# INA219_CH2.net
KiCad netlist of a schematic drawn in Altium Designer
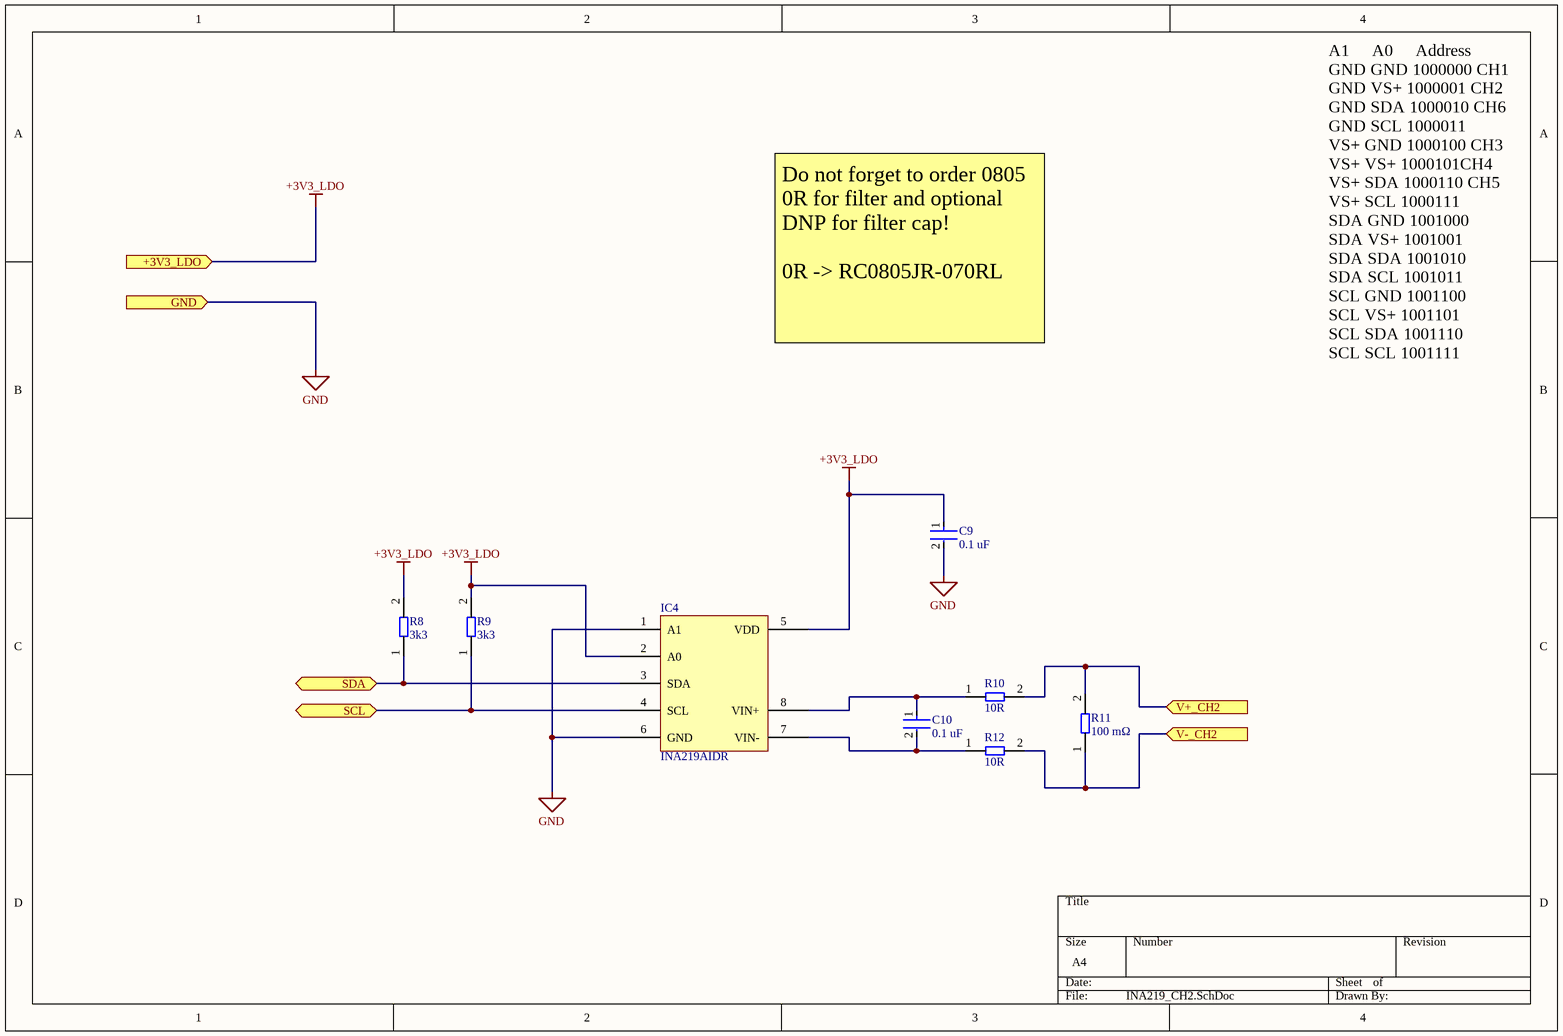
[diagram p0: INA219_CH2.SchDoc]

(export (version "E")
  (design (tool "Eeschema 10.0.6"))
  (components
    (comp (ref "C9")
      (value "0.1 uF")
      (footprint "FP-C0805C-DN-MFG")
      (description "C0805 0.10 μF X7R 30ppm/°C 20.00% 50 V C0805C104M5RAC")
      (fields
        (field (name "MANUFACTURER PART NUMBER") "C0805C104M5RAC")
        (field (name "MANUFACTURER") "KEMET")
      )
      (libsource (lib "Altium Content Vault") (part "b4654b650e69147ec39a6b967a45e02"))
    )
    (comp (ref "C10")
      (value "0.1 uF")
      (footprint "FP-C0805C-DN-MFG")
      (description "C0805 0.10 μF X7R 30ppm/°C 20.00% 50 V C0805C104M5RAC")
      (fields
        (field (name "MANUFACTURER PART NUMBER") "C0805C104M5RAC")
        (field (name "MANUFACTURER") "KEMET")
      )
      (libsource (lib "Altium Content Vault") (part "b4654b650e69147ec39a6b967a45e02"))
    )
    (comp (ref "IC4")
      (value "INA219AIDR")
      (footprint "INA219AIDR")
      (description "Current & Power Monitors & Regulators Zero-Drift,Bi-Dir Crnt/Pwr Monitor")
      (libsource (lib "Callisto Control Board") (part "INA219AIDR"))
    )
    (comp (ref "R8")
      (value "3k3")
      (footprint "0805 Resistor - IPC A")
      (description "Thick Film Resistors - SMD 3.3 kOhms 125 mW 0805 1%\r\nRE0805FRE073K3L")
      (libsource (lib "Callisto Control Board") (part "RE0805FRE073K3L"))
    )
    (comp (ref "R9")
      (value "3k3")
      (footprint "0805 Resistor - IPC A")
      (description "Thick Film Resistors - SMD 3.3 kOhms 125 mW 0805 1%\r\nRE0805FRE073K3L")
      (libsource (lib "Callisto Control Board") (part "RE0805FRE073K3L"))
    )
    (comp (ref "R10")
      (value "10R")
      (footprint "0805 Resistor - IPC A")
      (description "Thick Film Resistors - SMD 10 Ohms 125 mW 0805 1%\r\nRC0805FR-0710RL")
      (libsource (lib "Callisto Control Board") (part "RC0805FR-0710RL"))
    )
    (comp (ref "R11")
      (value "100 mΩ")
      (footprint "PE2512FKM070R1L")
      (description "Current Sense Resistors - SMD 100 mOhms 1 Watt 1 % 75 ppm/C AEC-Q200\r\nPE2512FKM070R1L")
      (libsource (lib "Callisto Control Board") (part "PE2512FKM070R1L"))
    )
    (comp (ref "R12")
      (value "10R")
      (footprint "0805 Resistor - IPC A")
      (description "Thick Film Resistors - SMD 10 Ohms 125 mW 0805 1%\r\nRC0805FR-0710RL")
      (libsource (lib "Callisto Control Board") (part "RC0805FR-0710RL"))
    )
  )
  (nets
    (net (code "1") (name "+3V3_LDO") (class "Default")
      (node (ref "C9") (pin "1") (pinfunction "1_1") (pintype "passive"))
      (node (ref "IC4") (pin "2") (pinfunction "A0_2") (pintype "passive"))
      (node (ref "IC4") (pin "5") (pinfunction "VDD_5") (pintype "passive"))
      (node (ref "R8") (pin "2") (pintype "passive"))
      (node (ref "R9") (pin "2") (pintype "passive"))
    )
    (net (code "2") (name "/SCL") (class "Default")
      (node (ref "IC4") (pin "4") (pinfunction "SCL_4") (pintype "passive"))
      (node (ref "R9") (pin "1") (pintype "passive"))
    )
    (net (code "3") (name "/SDA") (class "Default")
      (node (ref "IC4") (pin "3") (pinfunction "SDA_3") (pintype "passive"))
      (node (ref "R8") (pin "1") (pintype "passive"))
    )
    (net (code "4") (name "/V+_CH2") (class "Default")
      (node (ref "R10") (pin "2") (pintype "passive"))
      (node (ref "R11") (pin "2") (pintype "passive"))
    )
    (net (code "5") (name "/V-_CH2") (class "Default")
      (node (ref "R11") (pin "1") (pintype "passive"))
      (node (ref "R12") (pin "2") (pintype "passive"))
    )
    (net (code "6") (name "GND") (class "Default")
      (node (ref "C9") (pin "2") (pinfunction "2_2") (pintype "passive"))
      (node (ref "IC4") (pin "1") (pinfunction "A1_1") (pintype "passive"))
      (node (ref "IC4") (pin "6") (pinfunction "GND_6") (pintype "passive"))
    )
    (net (code "7") (name "Net-(IC4-VIN+)") (class "Default")
      (node (ref "C10") (pin "1") (pinfunction "1_1") (pintype "passive"))
      (node (ref "IC4") (pin "8") (pinfunction "VIN+_8") (pintype "passive"))
      (node (ref "R10") (pin "1") (pintype "passive"))
    )
    (net (code "8") (name "Net-(IC4-VIN-)") (class "Default")
      (node (ref "C10") (pin "2") (pinfunction "2_2") (pintype "passive"))
      (node (ref "IC4") (pin "7") (pinfunction "VIN-_7") (pintype "passive"))
      (node (ref "R12") (pin "1") (pintype "passive"))
    )
  )
)
